# CntrlBoard.net
KiCad netlist of a schematic drawn in EAGLE
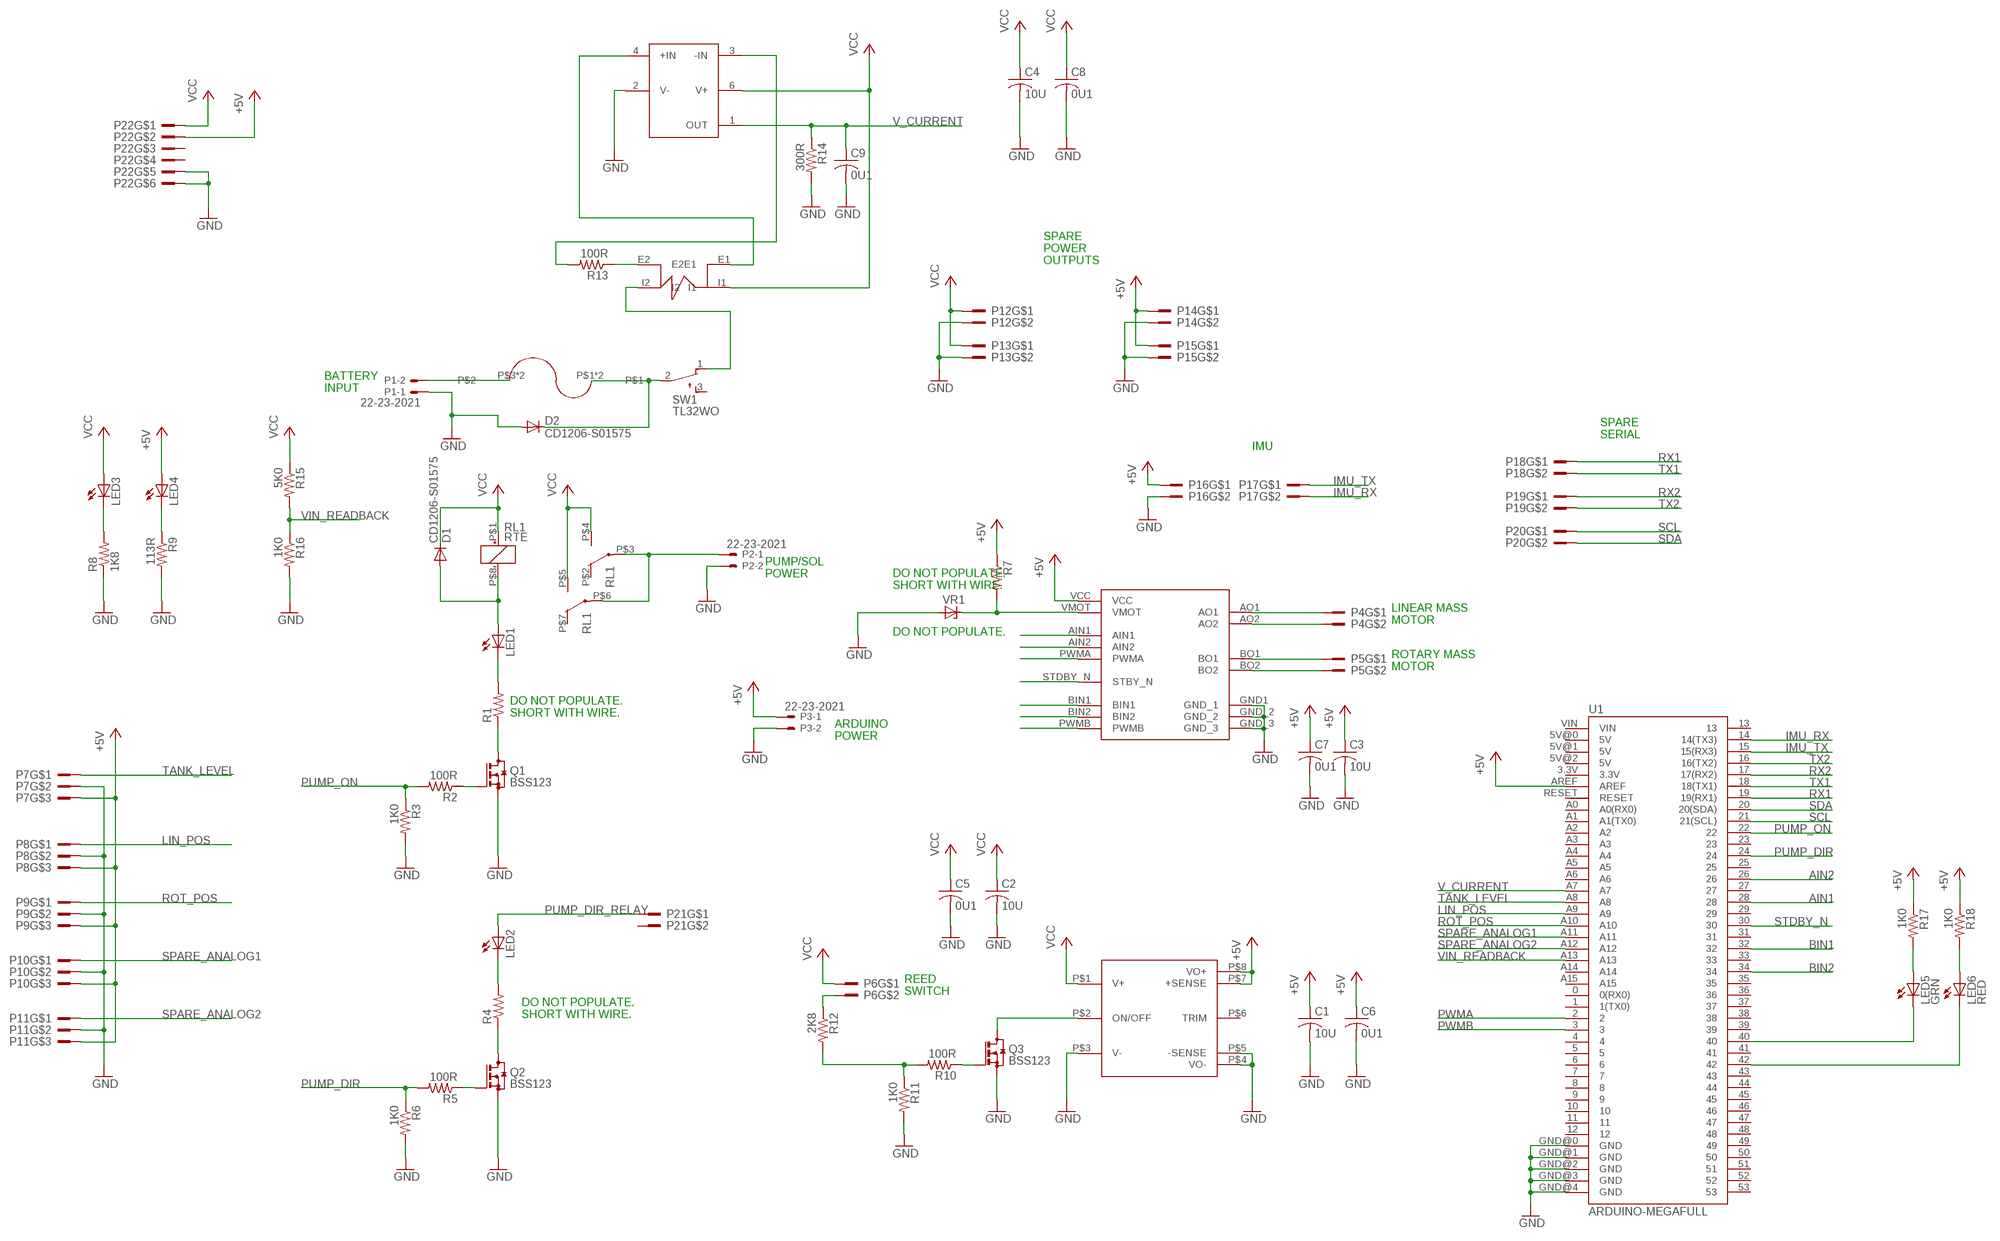
[diagram p0: schematic, sheet 1]

(export (version "E")
  (design (tool "Eeschema 10.0.6"))
  (components
    (comp (ref "C1")
      (value "10U")
      (footprint "eagle-import:C1210K")
      (libsource (lib "eagle-import") (part "C-USC1210K"))
    )
    (comp (ref "C2")
      (value "10U")
      (footprint "eagle-import:C1210K")
      (libsource (lib "eagle-import") (part "C-USC1210K"))
    )
    (comp (ref "C3")
      (value "10U")
      (footprint "eagle-import:C1210K")
      (libsource (lib "eagle-import") (part "C-USC1210K"))
    )
    (comp (ref "C4")
      (value "10U")
      (footprint "eagle-import:C1210K")
      (libsource (lib "eagle-import") (part "C-USC1210K"))
    )
    (comp (ref "C5")
      (value "0U1")
      (footprint "eagle-import:C1210K")
      (libsource (lib "eagle-import") (part "C-USC1210K"))
    )
    (comp (ref "C6")
      (value "0U1")
      (footprint "eagle-import:C1210K")
      (libsource (lib "eagle-import") (part "C-USC1210K"))
    )
    (comp (ref "C7")
      (value "0U1")
      (footprint "eagle-import:C1210K")
      (libsource (lib "eagle-import") (part "C-USC1210K"))
    )
    (comp (ref "C8")
      (value "0U1")
      (footprint "eagle-import:C1210K")
      (libsource (lib "eagle-import") (part "C-USC1210K"))
    )
    (comp (ref "C9")
      (value "0U1")
      (footprint "eagle-import:C1210K")
      (libsource (lib "eagle-import") (part "C-USC1210K"))
    )
    (comp (ref "D1")
      (value "CD1206-S01575")
      (footprint "eagle-import:CD1206")
      (libsource (lib "eagle-import") (part "CD1206-S01575"))
    )
    (comp (ref "D2")
      (value "CD1206-S01575")
      (footprint "eagle-import:CD1206")
      (libsource (lib "eagle-import") (part "CD1206-S01575"))
    )
    (comp (ref "LED1")
      (value "LEDCHIPLED_1206")
      (footprint "eagle-import:CHIPLED_1206")
      (libsource (lib "eagle-import") (part "LEDCHIPLED_1206"))
    )
    (comp (ref "LED2")
      (value "LEDCHIPLED_1206")
      (footprint "eagle-import:CHIPLED_1206")
      (libsource (lib "eagle-import") (part "LEDCHIPLED_1206"))
    )
    (comp (ref "LED3")
      (value "LEDCHIPLED_1206")
      (footprint "eagle-import:CHIPLED_1206")
      (libsource (lib "eagle-import") (part "LEDCHIPLED_1206"))
    )
    (comp (ref "LED4")
      (value "LEDCHIPLED_1206")
      (footprint "eagle-import:CHIPLED_1206")
      (libsource (lib "eagle-import") (part "LEDCHIPLED_1206"))
    )
    (comp (ref "LED5")
      (value "GRN")
      (footprint "eagle-import:CHIPLED_1206")
      (libsource (lib "eagle-import") (part "LEDCHIPLED_1206"))
    )
    (comp (ref "LED6")
      (value "RED")
      (footprint "eagle-import:CHIPLED_1206")
      (libsource (lib "eagle-import") (part "LEDCHIPLED_1206"))
    )
    (comp (ref "P1")
      (value "22-23-2021")
      (footprint "eagle-import:22-23-2021")
      (fields (field (name "MF") "MOLEX"))
      (libsource (lib "eagle-import") (part "22-23-2021"))
    )
    (comp (ref "P2")
      (value "22-23-2021")
      (footprint "eagle-import:22-23-2021")
      (fields (field (name "MF") "MOLEX"))
      (libsource (lib "eagle-import") (part "22-23-2021"))
    )
    (comp (ref "P3")
      (value "22-23-2021")
      (footprint "eagle-import:22-23-2021")
      (fields (field (name "MF") "MOLEX"))
      (libsource (lib "eagle-import") (part "22-23-2021"))
    )
    (comp (ref "P4")
      (value "DF3A-2P-2DSA")
      (footprint "eagle-import:DF3A-2P-2DSA")
      (libsource (lib "eagle-import") (part "DF3A-2P-2DSA"))
    )
    (comp (ref "P5")
      (value "DF3A-2P-2DSA")
      (footprint "eagle-import:DF3A-2P-2DSA")
      (libsource (lib "eagle-import") (part "DF3A-2P-2DSA"))
    )
    (comp (ref "P6")
      (value "DF3A-2P-2DSA")
      (footprint "eagle-import:DF3A-2P-2DSA")
      (libsource (lib "eagle-import") (part "DF3A-2P-2DSA"))
    )
    (comp (ref "P7")
      (value "3MM2MMLOCKING")
      (footprint "eagle-import:3PIN_2MMLOCKING")
      (libsource (lib "eagle-import") (part "3MM2MMLOCKING"))
    )
    (comp (ref "P8")
      (value "3MM2MMLOCKING")
      (footprint "eagle-import:3PIN_2MMLOCKING")
      (libsource (lib "eagle-import") (part "3MM2MMLOCKING"))
    )
    (comp (ref "P9")
      (value "3MM2MMLOCKING")
      (footprint "eagle-import:3PIN_2MMLOCKING")
      (libsource (lib "eagle-import") (part "3MM2MMLOCKING"))
    )
    (comp (ref "P10")
      (value "3MM2MMLOCKING")
      (footprint "eagle-import:3PIN_2MMLOCKING")
      (libsource (lib "eagle-import") (part "3MM2MMLOCKING"))
    )
    (comp (ref "P11")
      (value "3MM2MMLOCKING")
      (footprint "eagle-import:3PIN_2MMLOCKING")
      (libsource (lib "eagle-import") (part "3MM2MMLOCKING"))
    )
    (comp (ref "P12")
      (value "DF3A-2P-2DSA")
      (footprint "eagle-import:DF3A-2P-2DSA")
      (libsource (lib "eagle-import") (part "DF3A-2P-2DSA"))
    )
    (comp (ref "P13")
      (value "DF3A-2P-2DSA")
      (footprint "eagle-import:DF3A-2P-2DSA")
      (libsource (lib "eagle-import") (part "DF3A-2P-2DSA"))
    )
    (comp (ref "P14")
      (value "DF3A-2P-2DSA")
      (footprint "eagle-import:DF3A-2P-2DSA")
      (libsource (lib "eagle-import") (part "DF3A-2P-2DSA"))
    )
    (comp (ref "P15")
      (value "DF3A-2P-2DSA")
      (footprint "eagle-import:DF3A-2P-2DSA")
      (libsource (lib "eagle-import") (part "DF3A-2P-2DSA"))
    )
    (comp (ref "P16")
      (value "DF3A-2P-2DSA")
      (footprint "eagle-import:DF3A-2P-2DSA")
      (libsource (lib "eagle-import") (part "DF3A-2P-2DSA"))
    )
    (comp (ref "P17")
      (value "DF3A-2P-2DSA")
      (footprint "eagle-import:DF3A-2P-2DSA")
      (libsource (lib "eagle-import") (part "DF3A-2P-2DSA"))
    )
    (comp (ref "P18")
      (value "DF3A-2P-2DSA")
      (footprint "eagle-import:DF3A-2P-2DSA")
      (libsource (lib "eagle-import") (part "DF3A-2P-2DSA"))
    )
    (comp (ref "P19")
      (value "DF3A-2P-2DSA")
      (footprint "eagle-import:DF3A-2P-2DSA")
      (libsource (lib "eagle-import") (part "DF3A-2P-2DSA"))
    )
    (comp (ref "P20")
      (value "DF3A-2P-2DSA")
      (footprint "eagle-import:DF3A-2P-2DSA")
      (libsource (lib "eagle-import") (part "DF3A-2P-2DSA"))
    )
    (comp (ref "P21")
      (value "DF3A-2P-2DSA")
      (footprint "eagle-import:DF3A-2P-2DSA")
      (libsource (lib "eagle-import") (part "DF3A-2P-2DSA"))
    )
    (comp (ref "P22")
      (value "6PIN2ROWARDUINO")
      (footprint "eagle-import:6PIN2ROWARDUINO")
      (libsource (lib "eagle-import") (part "6PIN2ROWARDUINO"))
    )
    (comp (ref "PS1")
      (value "KHHD006A0A41Z")
      (footprint "eagle-import:KHHD006A0A41Z")
      (libsource (lib "eagle-import") (part "KHHD006A0A41Z"))
    )
    (comp (ref "Q1")
      (value "BSS123")
      (footprint "eagle-import:SOT23")
      (libsource (lib "eagle-import") (part "BSS123"))
    )
    (comp (ref "Q2")
      (value "BSS123")
      (footprint "eagle-import:SOT23")
      (libsource (lib "eagle-import") (part "BSS123"))
    )
    (comp (ref "Q3")
      (value "BSS123")
      (footprint "eagle-import:SOT23")
      (libsource (lib "eagle-import") (part "BSS123"))
    )
    (comp (ref "R1")
      (value "R-US_R1206")
      (footprint "eagle-import:R1206")
      (libsource (lib "eagle-import") (part "R-US_R1206"))
    )
    (comp (ref "R2")
      (value "100R")
      (footprint "eagle-import:R1206")
      (libsource (lib "eagle-import") (part "R-US_R1206"))
    )
    (comp (ref "R3")
      (value "1K0")
      (footprint "eagle-import:R1206")
      (libsource (lib "eagle-import") (part "R-US_R1206"))
    )
    (comp (ref "R4")
      (value "R-US_R1206")
      (footprint "eagle-import:R1206")
      (libsource (lib "eagle-import") (part "R-US_R1206"))
    )
    (comp (ref "R5")
      (value "100R")
      (footprint "eagle-import:R1206")
      (libsource (lib "eagle-import") (part "R-US_R1206"))
    )
    (comp (ref "R6")
      (value "1K0")
      (footprint "eagle-import:R1206")
      (libsource (lib "eagle-import") (part "R-US_R1206"))
    )
    (comp (ref "R7")
      (value "R-US_R1206")
      (footprint "eagle-import:R1206")
      (libsource (lib "eagle-import") (part "R-US_R1206"))
    )
    (comp (ref "R8")
      (value "1K8")
      (footprint "eagle-import:R1210")
      (libsource (lib "eagle-import") (part "R-US_R1210"))
    )
    (comp (ref "R9")
      (value "113R")
      (footprint "eagle-import:R1206")
      (libsource (lib "eagle-import") (part "R-US_R1206"))
    )
    (comp (ref "R10")
      (value "100R")
      (footprint "eagle-import:R1206")
      (libsource (lib "eagle-import") (part "R-US_R1206"))
    )
    (comp (ref "R11")
      (value "1K0")
      (footprint "eagle-import:R1206")
      (libsource (lib "eagle-import") (part "R-US_R1206"))
    )
    (comp (ref "R12")
      (value "2K8")
      (footprint "eagle-import:R1206")
      (libsource (lib "eagle-import") (part "R-US_R1206"))
    )
    (comp (ref "R13")
      (value "100R")
      (footprint "eagle-import:R1206")
      (libsource (lib "eagle-import") (part "R-US_R1206"))
    )
    (comp (ref "R14")
      (value "300R")
      (footprint "eagle-import:R1206")
      (libsource (lib "eagle-import") (part "R-US_R1206"))
    )
    (comp (ref "R15")
      (value "5K0")
      (footprint "eagle-import:R1206")
      (libsource (lib "eagle-import") (part "R-US_R1206"))
    )
    (comp (ref "R16")
      (value "1K0")
      (footprint "eagle-import:R1206")
      (libsource (lib "eagle-import") (part "R-US_R1206"))
    )
    (comp (ref "R17")
      (value "1K0")
      (footprint "eagle-import:R1206")
      (libsource (lib "eagle-import") (part "R-US_R1206"))
    )
    (comp (ref "R18")
      (value "1K0")
      (footprint "eagle-import:R1206")
      (libsource (lib "eagle-import") (part "R-US_R1206"))
    )
    (comp (ref "RL1")
      (value "RTE")
      (footprint "eagle-import:RTE")
      (libsource (lib "eagle-import") (part "RTE"))
    )
    (comp (ref "SW1")
      (value "TL32WO")
      (footprint "eagle-import:TL3XWO")
      (libsource (lib "eagle-import") (part "TL32WO"))
    )
    (comp (ref "U$1")
      (value "ATC_FUSE_HOLDER")
      (footprint "eagle-import:FUSE_HOLDER_ATC")
      (libsource (lib "eagle-import") (part "ATC_FUSE_HOLDER"))
    )
    (comp (ref "U$2")
      (value "POLOLU713")
      (footprint "eagle-import:POLOLU713")
      (libsource (lib "eagle-import") (part "POLOLU713"))
    )
    (comp (ref "U$3")
      (value "RSHUNT")
      (footprint "eagle-import:CM2512SHUNT")
      (libsource (lib "eagle-import") (part "RSHUNT"))
    )
    (comp (ref "U$4")
      (value "LT6106")
      (footprint "eagle-import:TSOT23-6")
      (libsource (lib "eagle-import") (part "LT6106"))
    )
    (comp (ref "U1")
      (value "ARDUINO-MEGAFULL")
      (footprint "eagle-import:ARDUINO_MEGA")
      (libsource (lib "eagle-import") (part "ARDUINO-MEGAFULL"))
    )
    (comp (ref "VR1")
      (value "ZENER-DIODESOT23")
      (footprint "eagle-import:SOT23")
      (libsource (lib "eagle-import") (part "ZENER-DIODESOT23"))
    )
  )
  (nets
    (net (code "1") (name "+5V") (class "Default")
      (node (ref "C1") (pin "1") (pinfunction "1_1") (pintype "passive"))
      (node (ref "C3") (pin "1") (pinfunction "1_1") (pintype "passive"))
      (node (ref "C6") (pin "1") (pinfunction "1_1") (pintype "passive"))
      (node (ref "C7") (pin "1") (pinfunction "1_1") (pintype "passive"))
      (node (ref "LED4") (pin "A") (pinfunction "A_A") (pintype "passive"))
      (node (ref "P10") (pin "P$3") (pinfunction "KL_P$3") (pintype "passive"))
      (node (ref "P11") (pin "P$3") (pinfunction "KL_P$3") (pintype "passive"))
      (node (ref "P14") (pin "P$1") (pinfunction "KL_P$1") (pintype "passive"))
      (node (ref "P15") (pin "P$1") (pinfunction "KL_P$1") (pintype "passive"))
      (node (ref "P16") (pin "P$1") (pinfunction "KL_P$1") (pintype "passive"))
      (node (ref "P22") (pin "P$2") (pinfunction "KL_P$2") (pintype "passive"))
      (node (ref "P3") (pin "1") (pinfunction "S_1") (pintype "passive"))
      (node (ref "P7") (pin "P$3") (pinfunction "KL_P$3") (pintype "passive"))
      (node (ref "P8") (pin "P$3") (pinfunction "KL_P$3") (pintype "passive"))
      (node (ref "P9") (pin "P$3") (pinfunction "KL_P$3") (pintype "passive"))
      (node (ref "PS1") (pin "P$7") (pinfunction "+SENSE_P$7") (pintype "bidirectional"))
      (node (ref "PS1") (pin "P$8") (pinfunction "VO+_P$8") (pintype "bidirectional"))
      (node (ref "R17") (pin "1") (pinfunction "1_1") (pintype "passive"))
      (node (ref "R18") (pin "1") (pinfunction "1_1") (pintype "passive"))
      (node (ref "R7") (pin "1") (pinfunction "1_1") (pintype "passive"))
      (node (ref "U$2") (pin "VCC") (pinfunction "VCC_VCC") (pintype "bidirectional"))
      (node (ref "U1") (pin "AREF") (pinfunction "AREF_AREF") (pintype "bidirectional"))
    )
    (net (code "2") (name "/AIN1") (class "Default")
      (node (ref "U$2") (pin "AIN1") (pinfunction "AIN1_AIN1") (pintype "bidirectional"))
      (node (ref "U1") (pin "28") (pinfunction "28_28") (pintype "bidirectional"))
    )
    (net (code "3") (name "/AIN2") (class "Default")
      (node (ref "U$2") (pin "AIN2") (pinfunction "AIN2_AIN2") (pintype "bidirectional"))
      (node (ref "U1") (pin "26") (pinfunction "26_26") (pintype "bidirectional"))
    )
    (net (code "4") (name "/BIN1") (class "Default")
      (node (ref "U$2") (pin "BIN1") (pinfunction "BIN1_BIN1") (pintype "bidirectional"))
      (node (ref "U1") (pin "32") (pinfunction "32_32") (pintype "bidirectional"))
    )
    (net (code "5") (name "/BIN2") (class "Default")
      (node (ref "U$2") (pin "BIN2") (pinfunction "BIN2_BIN2") (pintype "bidirectional"))
      (node (ref "U1") (pin "34") (pinfunction "34_34") (pintype "bidirectional"))
    )
    (net (code "6") (name "/IMU_RX") (class "Default")
      (node (ref "P17") (pin "P$2") (pinfunction "KL_P$2") (pintype "passive"))
      (node (ref "U1") (pin "14") (pinfunction "14(TX3)_14") (pintype "bidirectional"))
    )
    (net (code "7") (name "/IMU_TX") (class "Default")
      (node (ref "P17") (pin "P$1") (pinfunction "KL_P$1") (pintype "passive"))
      (node (ref "U1") (pin "15") (pinfunction "15(RX3)_15") (pintype "bidirectional"))
    )
    (net (code "8") (name "/LIN_POS") (class "Default")
      (node (ref "P8") (pin "P$1") (pinfunction "KL_P$1") (pintype "passive"))
      (node (ref "U1") (pin "A9") (pinfunction "A9_A9") (pintype "bidirectional"))
    )
    (net (code "9") (name "/PUMP_DIR") (class "Default")
      (node (ref "R5") (pin "2") (pinfunction "2_2") (pintype "passive"))
      (node (ref "R6") (pin "1") (pinfunction "1_1") (pintype "passive"))
      (node (ref "U1") (pin "24") (pinfunction "24_24") (pintype "bidirectional"))
    )
    (net (code "10") (name "/PUMP_DIR_RELAY") (class "Default")
      (node (ref "LED2") (pin "A") (pinfunction "A_A") (pintype "passive"))
      (node (ref "P21") (pin "P$1") (pinfunction "KL_P$1") (pintype "passive"))
    )
    (net (code "11") (name "/PUMP_ON") (class "Default")
      (node (ref "R2") (pin "2") (pinfunction "2_2") (pintype "passive"))
      (node (ref "R3") (pin "1") (pinfunction "1_1") (pintype "passive"))
      (node (ref "U1") (pin "22") (pinfunction "22_22") (pintype "bidirectional"))
    )
    (net (code "12") (name "/PWMA") (class "Default")
      (node (ref "U$2") (pin "PWMA") (pinfunction "PWMA_PWMA") (pintype "bidirectional"))
      (node (ref "U1") (pin "2") (pinfunction "2_2") (pintype "bidirectional"))
    )
    (net (code "13") (name "/PWMB") (class "Default")
      (node (ref "U$2") (pin "PWMB") (pinfunction "PWMB_PWMB") (pintype "bidirectional"))
      (node (ref "U1") (pin "3") (pinfunction "3_3") (pintype "bidirectional"))
    )
    (net (code "14") (name "/ROT_POS") (class "Default")
      (node (ref "P9") (pin "P$1") (pinfunction "KL_P$1") (pintype "passive"))
      (node (ref "U1") (pin "A10") (pinfunction "A10_A10") (pintype "bidirectional"))
    )
    (net (code "15") (name "/RX1") (class "Default")
      (node (ref "P18") (pin "P$1") (pinfunction "KL_P$1") (pintype "passive"))
      (node (ref "U1") (pin "19") (pinfunction "19(RX1)_19") (pintype "bidirectional"))
    )
    (net (code "16") (name "/RX2") (class "Default")
      (node (ref "P19") (pin "P$1") (pinfunction "KL_P$1") (pintype "passive"))
      (node (ref "U1") (pin "17") (pinfunction "17(RX2)_17") (pintype "bidirectional"))
    )
    (net (code "17") (name "/SCL") (class "Default")
      (node (ref "P20") (pin "P$1") (pinfunction "KL_P$1") (pintype "passive"))
      (node (ref "U1") (pin "21") (pinfunction "21(SCL)_21") (pintype "bidirectional"))
    )
    (net (code "18") (name "/SDA") (class "Default")
      (node (ref "P20") (pin "P$2") (pinfunction "KL_P$2") (pintype "passive"))
      (node (ref "U1") (pin "20") (pinfunction "20(SDA)_20") (pintype "bidirectional"))
    )
    (net (code "19") (name "/SPARE_ANALOG1") (class "Default")
      (node (ref "P10") (pin "P$1") (pinfunction "KL_P$1") (pintype "passive"))
      (node (ref "U1") (pin "A11") (pinfunction "A11_A11") (pintype "bidirectional"))
    )
    (net (code "20") (name "/SPARE_ANALOG2") (class "Default")
      (node (ref "P11") (pin "P$1") (pinfunction "KL_P$1") (pintype "passive"))
      (node (ref "U1") (pin "A12") (pinfunction "A12_A12") (pintype "bidirectional"))
    )
    (net (code "21") (name "/STDBY_N") (class "Default")
      (node (ref "U$2") (pin "STDBY_N") (pinfunction "STBY_N_STDBY_N") (pintype "bidirectional"))
      (node (ref "U1") (pin "30") (pinfunction "30_30") (pintype "bidirectional"))
    )
    (net (code "22") (name "/TANK_LEVEL") (class "Default")
      (node (ref "P7") (pin "P$1") (pinfunction "KL_P$1") (pintype "passive"))
      (node (ref "U1") (pin "A8") (pinfunction "A8_A8") (pintype "bidirectional"))
    )
    (net (code "23") (name "/TX1") (class "Default")
      (node (ref "P18") (pin "P$2") (pinfunction "KL_P$2") (pintype "passive"))
      (node (ref "U1") (pin "18") (pinfunction "18(TX1)_18") (pintype "bidirectional"))
    )
    (net (code "24") (name "/TX2") (class "Default")
      (node (ref "P19") (pin "P$2") (pinfunction "KL_P$2") (pintype "passive"))
      (node (ref "U1") (pin "16") (pinfunction "16(TX2)_16") (pintype "bidirectional"))
    )
    (net (code "25") (name "/VIN_READBACK") (class "Default")
      (node (ref "R15") (pin "2") (pinfunction "2_2") (pintype "passive"))
      (node (ref "R16") (pin "1") (pinfunction "1_1") (pintype "passive"))
      (node (ref "U1") (pin "A13") (pinfunction "A13_A13") (pintype "bidirectional"))
    )
    (net (code "26") (name "/V_CURRENT") (class "Default")
      (node (ref "C9") (pin "1") (pinfunction "1_1") (pintype "passive"))
      (node (ref "R14") (pin "1") (pinfunction "1_1") (pintype "passive"))
      (node (ref "U$4") (pin "1") (pinfunction "OUT_1") (pintype "bidirectional"))
      (node (ref "U1") (pin "A7") (pinfunction "A7_A7") (pintype "bidirectional"))
    )
    (net (code "27") (name "GND") (class "Default")
      (node (ref "C1") (pin "2") (pinfunction "2_2") (pintype "passive"))
      (node (ref "C2") (pin "2") (pinfunction "2_2") (pintype "passive"))
      (node (ref "C3") (pin "2") (pinfunction "2_2") (pintype "passive"))
      (node (ref "C4") (pin "2") (pinfunction "2_2") (pintype "passive"))
      (node (ref "C5") (pin "2") (pinfunction "2_2") (pintype "passive"))
      (node (ref "C6") (pin "2") (pinfunction "2_2") (pintype "passive"))
      (node (ref "C7") (pin "2") (pinfunction "2_2") (pintype "passive"))
      (node (ref "C8") (pin "2") (pinfunction "2_2") (pintype "passive"))
      (node (ref "C9") (pin "2") (pinfunction "2_2") (pintype "passive"))
      (node (ref "D2") (pin "A") (pinfunction "A_A") (pintype "passive"))
      (node (ref "P1") (pin "1") (pinfunction "S_1") (pintype "passive"))
      (node (ref "P10") (pin "P$2") (pinfunction "KL_P$2") (pintype "passive"))
      (node (ref "P11") (pin "P$2") (pinfunction "KL_P$2") (pintype "passive"))
      (node (ref "P12") (pin "P$2") (pinfunction "KL_P$2") (pintype "passive"))
      (node (ref "P13") (pin "P$2") (pinfunction "KL_P$2") (pintype "passive"))
      (node (ref "P14") (pin "P$2") (pinfunction "KL_P$2") (pintype "passive"))
      (node (ref "P15") (pin "P$2") (pinfunction "KL_P$2") (pintype "passive"))
      (node (ref "P16") (pin "P$2") (pinfunction "KL_P$2") (pintype "passive"))
      (node (ref "P2") (pin "2") (pinfunction "S_2") (pintype "passive"))
      (node (ref "P22") (pin "P$5") (pinfunction "KL_P$5") (pintype "passive"))
      (node (ref "P22") (pin "P$6") (pinfunction "KL_P$6") (pintype "passive"))
      (node (ref "P3") (pin "2") (pinfunction "S_2") (pintype "passive"))
      (node (ref "P7") (pin "P$2") (pinfunction "KL_P$2") (pintype "passive"))
      (node (ref "P8") (pin "P$2") (pinfunction "KL_P$2") (pintype "passive"))
      (node (ref "P9") (pin "P$2") (pinfunction "KL_P$2") (pintype "passive"))
      (node (ref "PS1") (pin "P$3") (pinfunction "V-_P$3") (pintype "bidirectional"))
      (node (ref "PS1") (pin "P$4") (pinfunction "VO-_P$4") (pintype "bidirectional"))
      (node (ref "PS1") (pin "P$5") (pinfunction "-SENSE_P$5") (pintype "bidirectional"))
      (node (ref "Q1") (pin "2") (pinfunction "S_2") (pintype "passive"))
      (node (ref "Q2") (pin "2") (pinfunction "S_2") (pintype "passive"))
      (node (ref "Q3") (pin "2") (pinfunction "S_2") (pintype "passive"))
      (node (ref "R11") (pin "2") (pinfunction "2_2") (pintype "passive"))
      (node (ref "R14") (pin "2") (pinfunction "2_2") (pintype "passive"))
      (node (ref "R16") (pin "2") (pinfunction "2_2") (pintype "passive"))
      (node (ref "R3") (pin "2") (pinfunction "2_2") (pintype "passive"))
      (node (ref "R6") (pin "2") (pinfunction "2_2") (pintype "passive"))
      (node (ref "R8") (pin "1") (pinfunction "1_1") (pintype "passive"))
      (node (ref "R9") (pin "2") (pinfunction "2_2") (pintype "passive"))
      (node (ref "U$2") (pin "GND1") (pinfunction "GND_1_GND1") (pintype "bidirectional"))
      (node (ref "U$2") (pin "GND_2") (pinfunction "GND_2_GND_2") (pintype "bidirectional"))
      (node (ref "U$2") (pin "GND_3") (pinfunction "GND_3_GND_3") (pintype "bidirectional"))
      (node (ref "U$4") (pin "2") (pinfunction "V-_2") (pintype "bidirectional"))
      (node (ref "U1") (pin "GND@0") (pinfunction "GND_GND@0") (pintype "bidirectional"))
      (node (ref "U1") (pin "GND@1") (pinfunction "GND_GND@1") (pintype "bidirectional"))
      (node (ref "U1") (pin "GND@2") (pinfunction "GND_GND@2") (pintype "bidirectional"))
      (node (ref "U1") (pin "GND@3") (pinfunction "GND_GND@3") (pintype "bidirectional"))
      (node (ref "U1") (pin "GND@4") (pinfunction "GND_GND@4") (pintype "bidirectional"))
      (node (ref "VR1") (pin "1") (pinfunction "A_1") (pintype "passive"))
    )
    (net (code "28") (name "Net-(D2-C)") (class "Default")
      (node (ref "D2") (pin "K") (pinfunction "C_K") (pintype "passive"))
      (node (ref "SW1") (pin "2") (pinfunction "P_2") (pintype "passive"))
      (node (ref "U$1") (pin "P$1") (pinfunction "P$1_P$1") (pintype "bidirectional"))
      (node (ref "U$1") (pin "P$2") (pinfunction "P$1_P$2") (pintype "bidirectional"))
    )
    (net (code "29") (name "Net-(LED1-PadC)") (class "Default")
      (node (ref "LED1") (pin "C") (pinfunction "C_C") (pintype "passive"))
      (node (ref "R1") (pin "2") (pinfunction "2_2") (pintype "passive"))
    )
    (net (code "30") (name "Net-(LED2-PadC)") (class "Default")
      (node (ref "LED2") (pin "C") (pinfunction "C_C") (pintype "passive"))
      (node (ref "R4") (pin "2") (pinfunction "2_2") (pintype "passive"))
    )
    (net (code "31") (name "Net-(LED3-PadC)") (class "Default")
      (node (ref "LED3") (pin "C") (pinfunction "C_C") (pintype "passive"))
      (node (ref "R8") (pin "2") (pinfunction "2_2") (pintype "passive"))
    )
    (net (code "32") (name "Net-(LED4-PadC)") (class "Default")
      (node (ref "LED4") (pin "C") (pinfunction "C_C") (pintype "passive"))
      (node (ref "R9") (pin "1") (pinfunction "1_1") (pintype "passive"))
    )
    (net (code "33") (name "Net-(LED5-PadA)") (class "Default")
      (node (ref "LED5") (pin "A") (pinfunction "A_A") (pintype "passive"))
      (node (ref "R17") (pin "2") (pinfunction "2_2") (pintype "passive"))
    )
    (net (code "34") (name "Net-(LED5-PadC)") (class "Default")
      (node (ref "LED5") (pin "C") (pinfunction "C_C") (pintype "passive"))
      (node (ref "U1") (pin "40") (pinfunction "40_40") (pintype "bidirectional"))
    )
    (net (code "35") (name "Net-(LED6-PadA)") (class "Default")
      (node (ref "LED6") (pin "A") (pinfunction "A_A") (pintype "passive"))
      (node (ref "R18") (pin "2") (pinfunction "2_2") (pintype "passive"))
    )
    (net (code "36") (name "Net-(LED6-PadC)") (class "Default")
      (node (ref "LED6") (pin "C") (pinfunction "C_C") (pintype "passive"))
      (node (ref "U1") (pin "42") (pinfunction "42_42") (pintype "bidirectional"))
    )
    (net (code "37") (name "Net-(P1B-S)") (class "Default")
      (node (ref "P1") (pin "2") (pinfunction "S_2") (pintype "passive"))
      (node (ref "U$1") (pin "P$3") (pinfunction "P$2_P$3") (pintype "bidirectional"))
      (node (ref "U$1") (pin "P$4") (pinfunction "P$2_P$4") (pintype "bidirectional"))
    )
    (net (code "38") (name "Net-(P2A-S)") (class "Default")
      (node (ref "P2") (pin "1") (pinfunction "S_1") (pintype "passive"))
      (node (ref "RL1") (pin "P$3") (pinfunction "P_P$3") (pintype "passive"))
      (node (ref "RL1") (pin "P$6") (pinfunction "P_P$6") (pintype "passive"))
    )
    (net (code "39") (name "Net-(P4A-KL)") (class "Default")
      (node (ref "P4") (pin "P$1") (pinfunction "KL_P$1") (pintype "passive"))
      (node (ref "U$2") (pin "AO1") (pinfunction "AO1_AO1") (pintype "bidirectional"))
    )
    (net (code "40") (name "Net-(P4B-KL)") (class "Default")
      (node (ref "P4") (pin "P$2") (pinfunction "KL_P$2") (pintype "passive"))
      (node (ref "U$2") (pin "AO2") (pinfunction "AO2_AO2") (pintype "bidirectional"))
    )
    (net (code "41") (name "Net-(P5A-KL)") (class "Default")
      (node (ref "P5") (pin "P$1") (pinfunction "KL_P$1") (pintype "passive"))
      (node (ref "U$2") (pin "BO1") (pinfunction "BO1_BO1") (pintype "bidirectional"))
    )
    (net (code "42") (name "Net-(P5B-KL)") (class "Default")
      (node (ref "P5") (pin "P$2") (pinfunction "KL_P$2") (pintype "passive"))
      (node (ref "U$2") (pin "BO2") (pinfunction "BO2_BO2") (pintype "bidirectional"))
    )
    (net (code "43") (name "Net-(P6B-KL)") (class "Default")
      (node (ref "P6") (pin "P$2") (pinfunction "KL_P$2") (pintype "passive"))
      (node (ref "R12") (pin "1") (pinfunction "1_1") (pintype "passive"))
    )
    (net (code "44") (name "Net-(PS1-ON{slash}OFF)") (class "Default")
      (node (ref "PS1") (pin "P$2") (pinfunction "ON/OFF_P$2") (pintype "bidirectional"))
      (node (ref "Q3") (pin "3") (pinfunction "D_3") (pintype "passive"))
    )
    (net (code "45") (name "Net-(Q1-D)") (class "Default")
      (node (ref "Q1") (pin "3") (pinfunction "D_3") (pintype "passive"))
      (node (ref "R1") (pin "1") (pinfunction "1_1") (pintype "passive"))
    )
    (net (code "46") (name "Net-(Q1-G)") (class "Default")
      (node (ref "Q1") (pin "1") (pinfunction "G_1") (pintype "passive"))
      (node (ref "R2") (pin "1") (pinfunction "1_1") (pintype "passive"))
    )
    (net (code "47") (name "Net-(Q2-D)") (class "Default")
      (node (ref "Q2") (pin "3") (pinfunction "D_3") (pintype "passive"))
      (node (ref "R4") (pin "1") (pinfunction "1_1") (pintype "passive"))
    )
    (net (code "48") (name "Net-(Q2-G)") (class "Default")
      (node (ref "Q2") (pin "1") (pinfunction "G_1") (pintype "passive"))
      (node (ref "R5") (pin "1") (pinfunction "1_1") (pintype "passive"))
    )
    (net (code "49") (name "Net-(Q3-G)") (class "Default")
      (node (ref "Q3") (pin "1") (pinfunction "G_1") (pintype "passive"))
      (node (ref "R10") (pin "1") (pinfunction "1_1") (pintype "passive"))
    )
    (net (code "50") (name "Net-(R10-Pad2)") (class "Default")
      (node (ref "R10") (pin "2") (pinfunction "2_2") (pintype "passive"))
      (node (ref "R11") (pin "1") (pinfunction "1_1") (pintype "passive"))
      (node (ref "R12") (pin "2") (pinfunction "2_2") (pintype "passive"))
    )
    (net (code "51") (name "Net-(R13-Pad1)") (class "Default")
      (node (ref "R13") (pin "1") (pinfunction "1_1") (pintype "passive"))
      (node (ref "U$3") (pin "E2") (pinfunction "E2_E2") (pintype "bidirectional"))
    )
    (net (code "52") (name "Net-(RL1A--)") (class "Default")
      (node (ref "D1") (pin "A") (pinfunction "A_A") (pintype "passive"))
      (node (ref "LED1") (pin "A") (pinfunction "A_A") (pintype "passive"))
      (node (ref "RL1") (pin "P$8") (pinfunction "-_P$8") (pintype "passive"))
    )
    (net (code "53") (name "Net-(SW1-O)") (class "Default")
      (node (ref "SW1") (pin "1") (pinfunction "O_1") (pintype "passive"))
      (node (ref "U$3") (pin "I2") (pinfunction "I2_I2") (pintype "bidirectional"))
    )
    (net (code "54") (name "Net-(U$4-+IN)") (class "Default")
      (node (ref "U$3") (pin "E1") (pinfunction "E1_E1") (pintype "bidirectional"))
      (node (ref "U$4") (pin "4") (pinfunction "+IN_4") (pintype "bidirectional"))
    )
    (net (code "55") (name "Net-(U$4--IN)") (class "Default")
      (node (ref "R13") (pin "2") (pinfunction "2_2") (pintype "passive"))
      (node (ref "U$4") (pin "3") (pinfunction "-IN_3") (pintype "bidirectional"))
    )
    (net (code "56") (name "Net-(VR1-C)") (class "Default")
      (node (ref "R7") (pin "2") (pinfunction "2_2") (pintype "passive"))
      (node (ref "U$2") (pin "VMOT") (pinfunction "VMOT_VMOT") (pintype "bidirectional"))
      (node (ref "VR1") (pin "3") (pinfunction "C_3") (pintype "passive"))
    )
    (net (code "57") (name "VCC") (class "Default")
      (node (ref "C2") (pin "1") (pinfunction "1_1") (pintype "passive"))
      (node (ref "C4") (pin "1") (pinfunction "1_1") (pintype "passive"))
      (node (ref "C5") (pin "1") (pinfunction "1_1") (pintype "passive"))
      (node (ref "C8") (pin "1") (pinfunction "1_1") (pintype "passive"))
      (node (ref "D1") (pin "K") (pinfunction "C_K") (pintype "passive"))
      (node (ref "LED3") (pin "A") (pinfunction "A_A") (pintype "passive"))
      (node (ref "P12") (pin "P$1") (pinfunction "KL_P$1") (pintype "passive"))
      (node (ref "P13") (pin "P$1") (pinfunction "KL_P$1") (pintype "passive"))
      (node (ref "P22") (pin "P$1") (pinfunction "KL_P$1") (pintype "passive"))
      (node (ref "P6") (pin "P$1") (pinfunction "KL_P$1") (pintype "passive"))
      (node (ref "PS1") (pin "P$1") (pinfunction "V+_P$1") (pintype "bidirectional"))
      (node (ref "R15") (pin "1") (pinfunction "1_1") (pintype "passive"))
      (node (ref "RL1") (pin "P$1") (pinfunction "+_P$1") (pintype "passive"))
      (node (ref "RL1") (pin "P$4") (pinfunction "S_P$4") (pintype "passive"))
      (node (ref "RL1") (pin "P$5") (pinfunction "S_P$5") (pintype "passive"))
      (node (ref "U$3") (pin "I1") (pinfunction "I1_I1") (pintype "bidirectional"))
      (node (ref "U$4") (pin "6") (pinfunction "V+_6") (pintype "bidirectional"))
    )
    (net (code "58") (name "unconnected-(P21B-KL-PadP$2)") (class "Default")
      (node (ref "P21") (pin "P$2") (pinfunction "KL_P$2") (pintype "passive"))
    )
    (net (code "59") (name "unconnected-(P22C-KL-PadP$3)") (class "Default")
      (node (ref "P22") (pin "P$3") (pinfunction "KL_P$3") (pintype "passive"))
    )
    (net (code "60") (name "unconnected-(P22D-KL-PadP$4)") (class "Default")
      (node (ref "P22") (pin "P$4") (pinfunction "KL_P$4") (pintype "passive"))
    )
    (net (code "61") (name "unconnected-(PS1-TRIM-PadP$6)") (class "Default")
      (node (ref "PS1") (pin "P$6") (pinfunction "TRIM_P$6") (pintype "bidirectional"))
    )
    (net (code "62") (name "unconnected-(RL1B-O-PadP$2)") (class "Default")
      (node (ref "RL1") (pin "P$2") (pinfunction "O_P$2") (pintype "passive"))
    )
    (net (code "63") (name "unconnected-(RL1C-O-PadP$7)") (class "Default")
      (node (ref "RL1") (pin "P$7") (pinfunction "O_P$7") (pintype "passive"))
    )
    (net (code "64") (name "unconnected-(SW1-S-Pad3)") (class "Default")
      (node (ref "SW1") (pin "3") (pinfunction "S_3") (pintype "passive"))
    )
    (net (code "65") (name "unconnected-(U1-0(RX0)-Pad0)") (class "Default")
      (node (ref "U1") (pin "0") (pinfunction "0(RX0)_0") (pintype "bidirectional"))
    )
    (net (code "66") (name "unconnected-(U1-1(TX0)-Pad1)") (class "Default")
      (node (ref "U1") (pin "1") (pinfunction "1(TX0)_1") (pintype "bidirectional"))
    )
    (net (code "67") (name "unconnected-(U1-5V-Pad5V@0)") (class "Default")
      (node (ref "U1") (pin "5V@0") (pinfunction "5V_5V@0") (pintype "bidirectional"))
    )
    (net (code "68") (name "unconnected-(U1-5V-Pad5V@1)") (class "Default")
      (node (ref "U1") (pin "5V@1") (pinfunction "5V_5V@1") (pintype "bidirectional"))
    )
    (net (code "69") (name "unconnected-(U1-5V-Pad5V@2)") (class "Default")
      (node (ref "U1") (pin "5V@2") (pinfunction "5V_5V@2") (pintype "bidirectional"))
    )
    (net (code "70") (name "unconnected-(U1-A0(RX0)-PadA0)") (class "Default")
      (node (ref "U1") (pin "A0") (pinfunction "A0(RX0)_A0") (pintype "bidirectional"))
    )
    (net (code "71") (name "unconnected-(U1-A1(TX0)-PadA1)") (class "Default")
      (node (ref "U1") (pin "A1") (pinfunction "A1(TX0)_A1") (pintype "bidirectional"))
    )
    (net (code "72") (name "unconnected-(U1-Pad3.3V)") (class "Default")
      (node (ref "U1") (pin "3.3V") (pinfunction "3.3V_3.3V") (pintype "bidirectional"))
    )
    (net (code "73") (name "unconnected-(U1-Pad4)") (class "Default")
      (node (ref "U1") (pin "4") (pinfunction "4_4") (pintype "bidirectional"))
    )
    (net (code "74") (name "unconnected-(U1-Pad5)") (class "Default")
      (node (ref "U1") (pin "5") (pinfunction "5_5") (pintype "bidirectional"))
    )
    (net (code "75") (name "unconnected-(U1-Pad6)") (class "Default")
      (node (ref "U1") (pin "6") (pinfunction "6_6") (pintype "bidirectional"))
    )
    (net (code "76") (name "unconnected-(U1-Pad7)") (class "Default")
      (node (ref "U1") (pin "7") (pinfunction "7_7") (pintype "bidirectional"))
    )
    (net (code "77") (name "unconnected-(U1-Pad8)") (class "Default")
      (node (ref "U1") (pin "8") (pinfunction "8_8") (pintype "bidirectional"))
    )
    (net (code "78") (name "unconnected-(U1-Pad9)") (class "Default")
      (node (ref "U1") (pin "9") (pinfunction "9_9") (pintype "bidirectional"))
    )
    (net (code "79") (name "unconnected-(U1-Pad10)") (class "Default")
      (node (ref "U1") (pin "10") (pinfunction "10_10") (pintype "bidirectional"))
    )
    (net (code "80") (name "unconnected-(U1-Pad11)") (class "Default")
      (node (ref "U1") (pin "11") (pinfunction "11_11") (pintype "bidirectional"))
    )
    (net (code "81") (name "unconnected-(U1-Pad12)") (class "Default")
      (node (ref "U1") (pin "12") (pinfunction "12_12") (pintype "bidirectional"))
    )
    (net (code "82") (name "unconnected-(U1-Pad13)") (class "Default")
      (node (ref "U1") (pin "13") (pinfunction "13_13") (pintype "bidirectional"))
    )
    (net (code "83") (name "unconnected-(U1-Pad23)") (class "Default")
      (node (ref "U1") (pin "23") (pinfunction "23_23") (pintype "bidirectional"))
    )
    (net (code "84") (name "unconnected-(U1-Pad25)") (class "Default")
      (node (ref "U1") (pin "25") (pinfunction "25_25") (pintype "bidirectional"))
    )
    (net (code "85") (name "unconnected-(U1-Pad27)") (class "Default")
      (node (ref "U1") (pin "27") (pinfunction "27_27") (pintype "bidirectional"))
    )
    (net (code "86") (name "unconnected-(U1-Pad29)") (class "Default")
      (node (ref "U1") (pin "29") (pinfunction "29_29") (pintype "bidirectional"))
    )
    (net (code "87") (name "unconnected-(U1-Pad31)") (class "Default")
      (node (ref "U1") (pin "31") (pinfunction "31_31") (pintype "bidirectional"))
    )
    (net (code "88") (name "unconnected-(U1-Pad33)") (class "Default")
      (node (ref "U1") (pin "33") (pinfunction "33_33") (pintype "bidirectional"))
    )
    (net (code "89") (name "unconnected-(U1-Pad35)") (class "Default")
      (node (ref "U1") (pin "35") (pinfunction "35_35") (pintype "bidirectional"))
    )
    (net (code "90") (name "unconnected-(U1-Pad36)") (class "Default")
      (node (ref "U1") (pin "36") (pinfunction "36_36") (pintype "bidirectional"))
    )
    (net (code "91") (name "unconnected-(U1-Pad37)") (class "Default")
      (node (ref "U1") (pin "37") (pinfunction "37_37") (pintype "bidirectional"))
    )
    (net (code "92") (name "unconnected-(U1-Pad38)") (class "Default")
      (node (ref "U1") (pin "38") (pinfunction "38_38") (pintype "bidirectional"))
    )
    (net (code "93") (name "unconnected-(U1-Pad39)") (class "Default")
      (node (ref "U1") (pin "39") (pinfunction "39_39") (pintype "bidirectional"))
    )
    (net (code "94") (name "unconnected-(U1-Pad41)") (class "Default")
      (node (ref "U1") (pin "41") (pinfunction "41_41") (pintype "bidirectional"))
    )
    (net (code "95") (name "unconnected-(U1-Pad43)") (class "Default")
      (node (ref "U1") (pin "43") (pinfunction "43_43") (pintype "bidirectional"))
    )
    (net (code "96") (name "unconnected-(U1-Pad44)") (class "Default")
      (node (ref "U1") (pin "44") (pinfunction "44_44") (pintype "bidirectional"))
    )
    (net (code "97") (name "unconnected-(U1-Pad45)") (class "Default")
      (node (ref "U1") (pin "45") (pinfunction "45_45") (pintype "bidirectional"))
    )
    (net (code "98") (name "unconnected-(U1-Pad46)") (class "Default")
      (node (ref "U1") (pin "46") (pinfunction "46_46") (pintype "bidirectional"))
    )
    (net (code "99") (name "unconnected-(U1-Pad47)") (class "Default")
      (node (ref "U1") (pin "47") (pinfunction "47_47") (pintype "bidirectional"))
    )
    (net (code "100") (name "unconnected-(U1-Pad48)") (class "Default")
      (node (ref "U1") (pin "48") (pinfunction "48_48") (pintype "bidirectional"))
    )
    (net (code "101") (name "unconnected-(U1-Pad49)") (class "Default")
      (node (ref "U1") (pin "49") (pinfunction "49_49") (pintype "bidirectional"))
    )
    (net (code "102") (name "unconnected-(U1-Pad50)") (class "Default")
      (node (ref "U1") (pin "50") (pinfunction "50_50") (pintype "bidirectional"))
    )
    (net (code "103") (name "unconnected-(U1-Pad51)") (class "Default")
      (node (ref "U1") (pin "51") (pinfunction "51_51") (pintype "bidirectional"))
    )
    (net (code "104") (name "unconnected-(U1-Pad52)") (class "Default")
      (node (ref "U1") (pin "52") (pinfunction "52_52") (pintype "bidirectional"))
    )
    (net (code "105") (name "unconnected-(U1-Pad53)") (class "Default")
      (node (ref "U1") (pin "53") (pinfunction "53_53") (pintype "bidirectional"))
    )
    (net (code "106") (name "unconnected-(U1-PadA2)") (class "Default")
      (node (ref "U1") (pin "A2") (pinfunction "A2_A2") (pintype "bidirectional"))
    )
    (net (code "107") (name "unconnected-(U1-PadA3)") (class "Default")
      (node (ref "U1") (pin "A3") (pinfunction "A3_A3") (pintype "bidirectional"))
    )
    (net (code "108") (name "unconnected-(U1-PadA4)") (class "Default")
      (node (ref "U1") (pin "A4") (pinfunction "A4_A4") (pintype "bidirectional"))
    )
    (net (code "109") (name "unconnected-(U1-PadA5)") (class "Default")
      (node (ref "U1") (pin "A5") (pinfunction "A5_A5") (pintype "bidirectional"))
    )
    (net (code "110") (name "unconnected-(U1-PadA6)") (class "Default")
      (node (ref "U1") (pin "A6") (pinfunction "A6_A6") (pintype "bidirectional"))
    )
    (net (code "111") (name "unconnected-(U1-PadA14)") (class "Default")
      (node (ref "U1") (pin "A14") (pinfunction "A14_A14") (pintype "bidirectional"))
    )
    (net (code "112") (name "unconnected-(U1-PadA15)") (class "Default")
      (node (ref "U1") (pin "A15") (pinfunction "A15_A15") (pintype "bidirectional"))
    )
    (net (code "113") (name "unconnected-(U1-PadRESET)") (class "Default")
      (node (ref "U1") (pin "RESET") (pinfunction "RESET_RESET") (pintype "bidirectional"))
    )
    (net (code "114") (name "unconnected-(U1-PadVIN)") (class "Default")
      (node (ref "U1") (pin "VIN") (pinfunction "VIN_VIN") (pintype "bidirectional"))
    )
  )
)
